# fmc-host-io-breakout.net
KiCad netlist of a schematic drawn in EAGLE
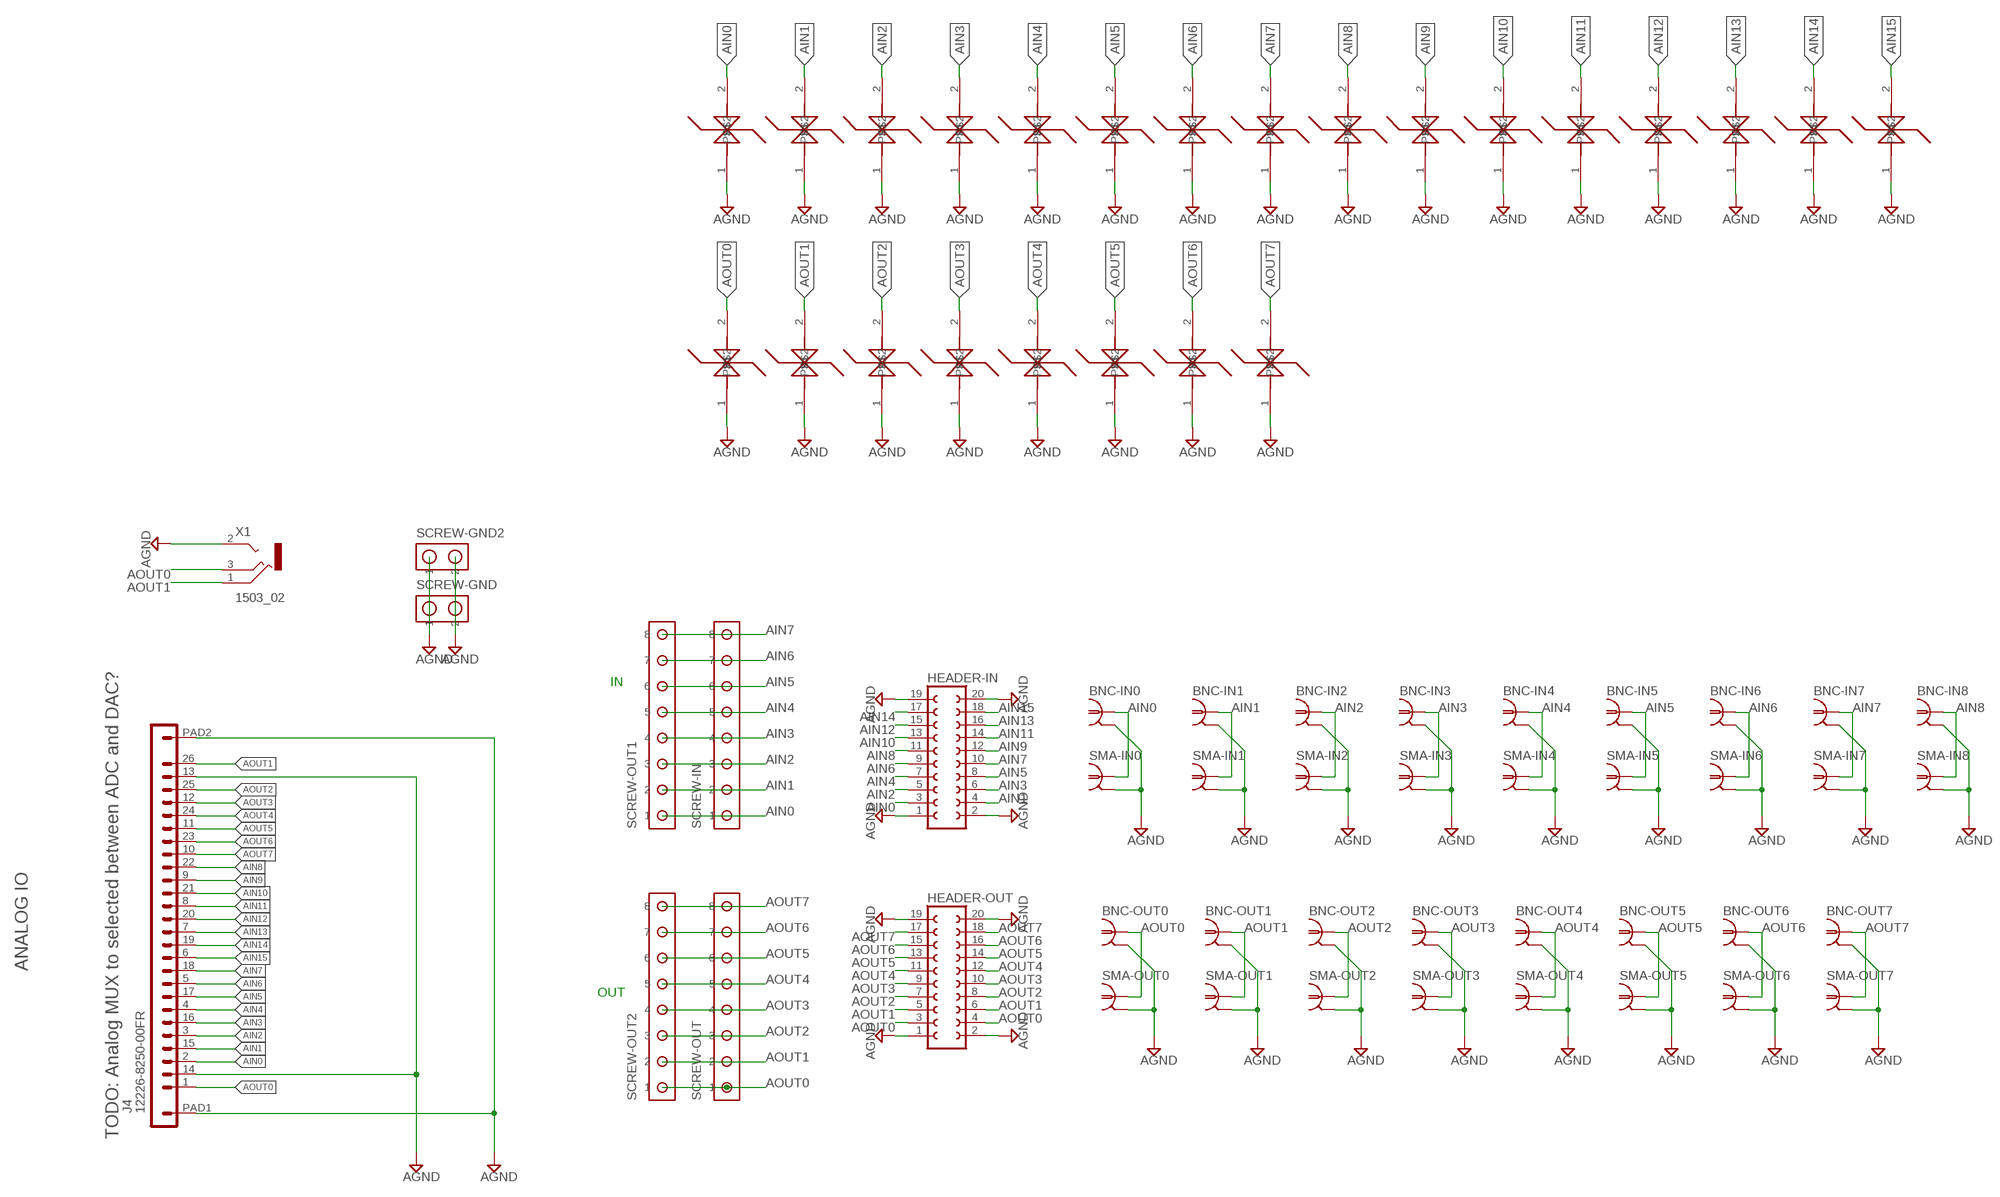
[diagram p0: schematic, sheet 1, part 1 of 2]
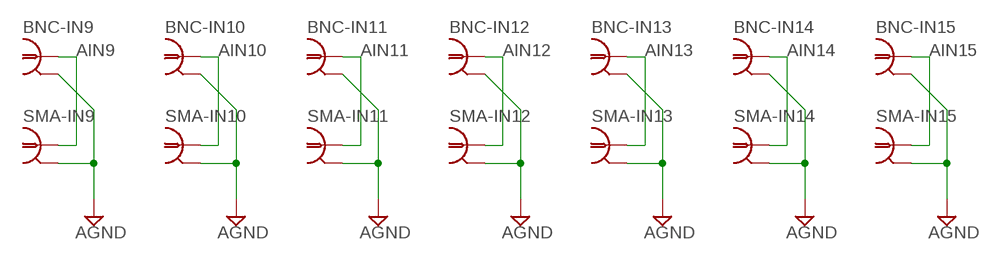
[diagram p1: schematic, sheet 1, part 2 of 2]

(export (version "E")
  (design (tool "Eeschema 10.0.6"))
  (components
    (comp (ref "BNC-IN0")
      (value "COAX_B35N61")
      (footprint "eagle-import:B35N61")
      (libsource (lib "eagle-import") (part "COAX_B35N61"))
    )
    (comp (ref "BNC-IN1")
      (value "COAX_B35N61")
      (footprint "eagle-import:B35N61")
      (libsource (lib "eagle-import") (part "COAX_B35N61"))
    )
    (comp (ref "BNC-IN2")
      (value "COAX_B35N61")
      (footprint "eagle-import:B35N61")
      (libsource (lib "eagle-import") (part "COAX_B35N61"))
    )
    (comp (ref "BNC-IN3")
      (value "COAX_B35N61")
      (footprint "eagle-import:B35N61")
      (libsource (lib "eagle-import") (part "COAX_B35N61"))
    )
    (comp (ref "BNC-IN4")
      (value "COAX_B35N61")
      (footprint "eagle-import:B35N61")
      (libsource (lib "eagle-import") (part "COAX_B35N61"))
    )
    (comp (ref "BNC-IN5")
      (value "COAX_B35N61")
      (footprint "eagle-import:B35N61")
      (libsource (lib "eagle-import") (part "COAX_B35N61"))
    )
    (comp (ref "BNC-IN6")
      (value "COAX_B35N61")
      (footprint "eagle-import:B35N61")
      (libsource (lib "eagle-import") (part "COAX_B35N61"))
    )
    (comp (ref "BNC-IN7")
      (value "COAX_B35N61")
      (footprint "eagle-import:B35N61")
      (libsource (lib "eagle-import") (part "COAX_B35N61"))
    )
    (comp (ref "BNC-IN8")
      (value "COAX_B35N61")
      (footprint "eagle-import:B35N61")
      (libsource (lib "eagle-import") (part "COAX_B35N61"))
    )
    (comp (ref "BNC-IN9")
      (value "COAX_B35N61")
      (footprint "eagle-import:B35N61")
      (libsource (lib "eagle-import") (part "COAX_B35N61"))
    )
    (comp (ref "BNC-IN10")
      (value "COAX_B35N61")
      (footprint "eagle-import:B35N61")
      (libsource (lib "eagle-import") (part "COAX_B35N61"))
    )
    (comp (ref "BNC-IN11")
      (value "COAX_B35N61")
      (footprint "eagle-import:B35N61")
      (libsource (lib "eagle-import") (part "COAX_B35N61"))
    )
    (comp (ref "BNC-IN12")
      (value "COAX_B35N61")
      (footprint "eagle-import:B35N61")
      (libsource (lib "eagle-import") (part "COAX_B35N61"))
    )
    (comp (ref "BNC-IN13")
      (value "COAX_B35N61")
      (footprint "eagle-import:B35N61")
      (libsource (lib "eagle-import") (part "COAX_B35N61"))
    )
    (comp (ref "BNC-IN14")
      (value "COAX_B35N61")
      (footprint "eagle-import:B35N61")
      (libsource (lib "eagle-import") (part "COAX_B35N61"))
    )
    (comp (ref "BNC-IN15")
      (value "COAX_B35N61")
      (footprint "eagle-import:B35N61")
      (libsource (lib "eagle-import") (part "COAX_B35N61"))
    )
    (comp (ref "BNC-OUT0")
      (value "COAX_B35N61")
      (footprint "eagle-import:B35N61")
      (libsource (lib "eagle-import") (part "COAX_B35N61"))
    )
    (comp (ref "BNC-OUT1")
      (value "COAX_B35N61")
      (footprint "eagle-import:B35N61")
      (libsource (lib "eagle-import") (part "COAX_B35N61"))
    )
    (comp (ref "BNC-OUT2")
      (value "COAX_B35N61")
      (footprint "eagle-import:B35N61")
      (libsource (lib "eagle-import") (part "COAX_B35N61"))
    )
    (comp (ref "BNC-OUT3")
      (value "COAX_B35N61")
      (footprint "eagle-import:B35N61")
      (libsource (lib "eagle-import") (part "COAX_B35N61"))
    )
    (comp (ref "BNC-OUT4")
      (value "COAX_B35N61")
      (footprint "eagle-import:B35N61")
      (libsource (lib "eagle-import") (part "COAX_B35N61"))
    )
    (comp (ref "BNC-OUT5")
      (value "COAX_B35N61")
      (footprint "eagle-import:B35N61")
      (libsource (lib "eagle-import") (part "COAX_B35N61"))
    )
    (comp (ref "BNC-OUT6")
      (value "COAX_B35N61")
      (footprint "eagle-import:B35N61")
      (libsource (lib "eagle-import") (part "COAX_B35N61"))
    )
    (comp (ref "BNC-OUT7")
      (value "COAX_B35N61")
      (footprint "eagle-import:B35N61")
      (libsource (lib "eagle-import") (part "COAX_B35N61"))
    )
    (comp (ref "HEADER-IN")
      (value "FE10-2")
      (footprint "eagle-import:FE10-2")
      (libsource (lib "eagle-import") (part "FE10-2"))
    )
    (comp (ref "HEADER-OUT")
      (value "FE10-2")
      (footprint "eagle-import:FE10-2")
      (libsource (lib "eagle-import") (part "FE10-2"))
    )
    (comp (ref "J4")
      (value "12226-8250-00FR")
      (footprint "eagle-import:12226-82X0-00XX")
      (libsource (lib "eagle-import") (part "PINHD-1X26_122"))
    )
    (comp (ref "SCREW-GND")
      (value "SCREW2")
      (footprint "eagle-import:SCREW2")
      (libsource (lib "eagle-import") (part "SCREW2"))
    )
    (comp (ref "SCREW-GND2")
      (value "SCREW2")
      (footprint "eagle-import:SCREW2")
      (libsource (lib "eagle-import") (part "SCREW2"))
    )
    (comp (ref "SCREW-IN")
      (value "SCREW8")
      (footprint "eagle-import:SCREW8")
      (libsource (lib "eagle-import") (part "SCREW8"))
    )
    (comp (ref "SCREW-OUT")
      (value "SCREW8")
      (footprint "eagle-import:SCREW8")
      (libsource (lib "eagle-import") (part "SCREW8"))
    )
    (comp (ref "SCREW-OUT1")
      (value "SCREW8")
      (footprint "eagle-import:SCREW8")
      (libsource (lib "eagle-import") (part "SCREW8"))
    )
    (comp (ref "SCREW-OUT2")
      (value "SCREW8")
      (footprint "eagle-import:SCREW8")
      (libsource (lib "eagle-import") (part "SCREW8"))
    )
    (comp (ref "SMA-IN0")
      (value "COAX_SMA-VERT")
      (footprint "eagle-import:SMA_JACK_142-0701-201")
      (libsource (lib "eagle-import") (part "COAX_SMA-VERT"))
    )
    (comp (ref "SMA-IN1")
      (value "COAX_SMA-VERT")
      (footprint "eagle-import:SMA_JACK_142-0701-201")
      (libsource (lib "eagle-import") (part "COAX_SMA-VERT"))
    )
    (comp (ref "SMA-IN2")
      (value "COAX_SMA-VERT")
      (footprint "eagle-import:SMA_JACK_142-0701-201")
      (libsource (lib "eagle-import") (part "COAX_SMA-VERT"))
    )
    (comp (ref "SMA-IN3")
      (value "COAX_SMA-VERT")
      (footprint "eagle-import:SMA_JACK_142-0701-201")
      (libsource (lib "eagle-import") (part "COAX_SMA-VERT"))
    )
    (comp (ref "SMA-IN4")
      (value "COAX_SMA-VERT")
      (footprint "eagle-import:SMA_JACK_142-0701-201")
      (libsource (lib "eagle-import") (part "COAX_SMA-VERT"))
    )
    (comp (ref "SMA-IN5")
      (value "COAX_SMA-VERT")
      (footprint "eagle-import:SMA_JACK_142-0701-201")
      (libsource (lib "eagle-import") (part "COAX_SMA-VERT"))
    )
    (comp (ref "SMA-IN6")
      (value "COAX_SMA-VERT")
      (footprint "eagle-import:SMA_JACK_142-0701-201")
      (libsource (lib "eagle-import") (part "COAX_SMA-VERT"))
    )
    (comp (ref "SMA-IN7")
      (value "COAX_SMA-VERT")
      (footprint "eagle-import:SMA_JACK_142-0701-201")
      (libsource (lib "eagle-import") (part "COAX_SMA-VERT"))
    )
    (comp (ref "SMA-IN8")
      (value "COAX_SMA-VERT")
      (footprint "eagle-import:SMA_JACK_142-0701-201")
      (libsource (lib "eagle-import") (part "COAX_SMA-VERT"))
    )
    (comp (ref "SMA-IN9")
      (value "COAX_SMA-VERT")
      (footprint "eagle-import:SMA_JACK_142-0701-201")
      (libsource (lib "eagle-import") (part "COAX_SMA-VERT"))
    )
    (comp (ref "SMA-IN10")
      (value "COAX_SMA-VERT")
      (footprint "eagle-import:SMA_JACK_142-0701-201")
      (libsource (lib "eagle-import") (part "COAX_SMA-VERT"))
    )
    (comp (ref "SMA-IN11")
      (value "COAX_SMA-VERT")
      (footprint "eagle-import:SMA_JACK_142-0701-201")
      (libsource (lib "eagle-import") (part "COAX_SMA-VERT"))
    )
    (comp (ref "SMA-IN12")
      (value "COAX_SMA-VERT")
      (footprint "eagle-import:SMA_JACK_142-0701-201")
      (libsource (lib "eagle-import") (part "COAX_SMA-VERT"))
    )
    (comp (ref "SMA-IN13")
      (value "COAX_SMA-VERT")
      (footprint "eagle-import:SMA_JACK_142-0701-201")
      (libsource (lib "eagle-import") (part "COAX_SMA-VERT"))
    )
    (comp (ref "SMA-IN14")
      (value "COAX_SMA-VERT")
      (footprint "eagle-import:SMA_JACK_142-0701-201")
      (libsource (lib "eagle-import") (part "COAX_SMA-VERT"))
    )
    (comp (ref "SMA-IN15")
      (value "COAX_SMA-VERT")
      (footprint "eagle-import:SMA_JACK_142-0701-201")
      (libsource (lib "eagle-import") (part "COAX_SMA-VERT"))
    )
    (comp (ref "SMA-OUT0")
      (value "COAX_SMA-VERT")
      (footprint "eagle-import:SMA_JACK_142-0701-201")
      (libsource (lib "eagle-import") (part "COAX_SMA-VERT"))
    )
    (comp (ref "SMA-OUT1")
      (value "COAX_SMA-VERT")
      (footprint "eagle-import:SMA_JACK_142-0701-201")
      (libsource (lib "eagle-import") (part "COAX_SMA-VERT"))
    )
    (comp (ref "SMA-OUT2")
      (value "COAX_SMA-VERT")
      (footprint "eagle-import:SMA_JACK_142-0701-201")
      (libsource (lib "eagle-import") (part "COAX_SMA-VERT"))
    )
    (comp (ref "SMA-OUT3")
      (value "COAX_SMA-VERT")
      (footprint "eagle-import:SMA_JACK_142-0701-201")
      (libsource (lib "eagle-import") (part "COAX_SMA-VERT"))
    )
    (comp (ref "SMA-OUT4")
      (value "COAX_SMA-VERT")
      (footprint "eagle-import:SMA_JACK_142-0701-201")
      (libsource (lib "eagle-import") (part "COAX_SMA-VERT"))
    )
    (comp (ref "SMA-OUT5")
      (value "COAX_SMA-VERT")
      (footprint "eagle-import:SMA_JACK_142-0701-201")
      (libsource (lib "eagle-import") (part "COAX_SMA-VERT"))
    )
    (comp (ref "SMA-OUT6")
      (value "COAX_SMA-VERT")
      (footprint "eagle-import:SMA_JACK_142-0701-201")
      (libsource (lib "eagle-import") (part "COAX_SMA-VERT"))
    )
    (comp (ref "SMA-OUT7")
      (value "COAX_SMA-VERT")
      (footprint "eagle-import:SMA_JACK_142-0701-201")
      (libsource (lib "eagle-import") (part "COAX_SMA-VERT"))
    )
    (comp (ref "U$1")
      (value "DIODE-ESD-BIDIRECTIONALDO-214AA")
      (footprint "eagle-import:DIOC7026X260")
      (libsource (lib "eagle-import") (part "DIODE-ESD-BIDIRECTIONALDO-214AA"))
    )
    (comp (ref "U$2")
      (value "DIODE-ESD-BIDIRECTIONALDO-214AA")
      (footprint "eagle-import:DIOC7026X260")
      (libsource (lib "eagle-import") (part "DIODE-ESD-BIDIRECTIONALDO-214AA"))
    )
    (comp (ref "U$3")
      (value "DIODE-ESD-BIDIRECTIONALDO-214AA")
      (footprint "eagle-import:DIOC7026X260")
      (libsource (lib "eagle-import") (part "DIODE-ESD-BIDIRECTIONALDO-214AA"))
    )
    (comp (ref "U$4")
      (value "DIODE-ESD-BIDIRECTIONALDO-214AA")
      (footprint "eagle-import:DIOC7026X260")
      (libsource (lib "eagle-import") (part "DIODE-ESD-BIDIRECTIONALDO-214AA"))
    )
    (comp (ref "U$5")
      (value "DIODE-ESD-BIDIRECTIONALDO-214AA")
      (footprint "eagle-import:DIOC7026X260")
      (libsource (lib "eagle-import") (part "DIODE-ESD-BIDIRECTIONALDO-214AA"))
    )
    (comp (ref "U$6")
      (value "DIODE-ESD-BIDIRECTIONALDO-214AA")
      (footprint "eagle-import:DIOC7026X260")
      (libsource (lib "eagle-import") (part "DIODE-ESD-BIDIRECTIONALDO-214AA"))
    )
    (comp (ref "U$7")
      (value "DIODE-ESD-BIDIRECTIONALDO-214AA")
      (footprint "eagle-import:DIOC7026X260")
      (libsource (lib "eagle-import") (part "DIODE-ESD-BIDIRECTIONALDO-214AA"))
    )
    (comp (ref "U$8")
      (value "DIODE-ESD-BIDIRECTIONALDO-214AA")
      (footprint "eagle-import:DIOC7026X260")
      (libsource (lib "eagle-import") (part "DIODE-ESD-BIDIRECTIONALDO-214AA"))
    )
    (comp (ref "U$9")
      (value "DIODE-ESD-BIDIRECTIONALDO-214AA")
      (footprint "eagle-import:DIOC7026X260")
      (libsource (lib "eagle-import") (part "DIODE-ESD-BIDIRECTIONALDO-214AA"))
    )
    (comp (ref "U$10")
      (value "DIODE-ESD-BIDIRECTIONALDO-214AA")
      (footprint "eagle-import:DIOC7026X260")
      (libsource (lib "eagle-import") (part "DIODE-ESD-BIDIRECTIONALDO-214AA"))
    )
    (comp (ref "U$11")
      (value "DIODE-ESD-BIDIRECTIONALDO-214AA")
      (footprint "eagle-import:DIOC7026X260")
      (libsource (lib "eagle-import") (part "DIODE-ESD-BIDIRECTIONALDO-214AA"))
    )
    (comp (ref "U$12")
      (value "DIODE-ESD-BIDIRECTIONALDO-214AA")
      (footprint "eagle-import:DIOC7026X260")
      (libsource (lib "eagle-import") (part "DIODE-ESD-BIDIRECTIONALDO-214AA"))
    )
    (comp (ref "U$13")
      (value "DIODE-ESD-BIDIRECTIONALDO-214AA")
      (footprint "eagle-import:DIOC7026X260")
      (libsource (lib "eagle-import") (part "DIODE-ESD-BIDIRECTIONALDO-214AA"))
    )
    (comp (ref "U$14")
      (value "DIODE-ESD-BIDIRECTIONALDO-214AA")
      (footprint "eagle-import:DIOC7026X260")
      (libsource (lib "eagle-import") (part "DIODE-ESD-BIDIRECTIONALDO-214AA"))
    )
    (comp (ref "U$15")
      (value "DIODE-ESD-BIDIRECTIONALDO-214AA")
      (footprint "eagle-import:DIOC7026X260")
      (libsource (lib "eagle-import") (part "DIODE-ESD-BIDIRECTIONALDO-214AA"))
    )
    (comp (ref "U$16")
      (value "DIODE-ESD-BIDIRECTIONALDO-214AA")
      (footprint "eagle-import:DIOC7026X260")
      (libsource (lib "eagle-import") (part "DIODE-ESD-BIDIRECTIONALDO-214AA"))
    )
    (comp (ref "U$17")
      (value "DIODE-ESD-BIDIRECTIONALDO-214AA")
      (footprint "eagle-import:DIOC7026X260")
      (libsource (lib "eagle-import") (part "DIODE-ESD-BIDIRECTIONALDO-214AA"))
    )
    (comp (ref "U$18")
      (value "DIODE-ESD-BIDIRECTIONALDO-214AA")
      (footprint "eagle-import:DIOC7026X260")
      (libsource (lib "eagle-import") (part "DIODE-ESD-BIDIRECTIONALDO-214AA"))
    )
    (comp (ref "U$19")
      (value "DIODE-ESD-BIDIRECTIONALDO-214AA")
      (footprint "eagle-import:DIOC7026X260")
      (libsource (lib "eagle-import") (part "DIODE-ESD-BIDIRECTIONALDO-214AA"))
    )
    (comp (ref "U$20")
      (value "DIODE-ESD-BIDIRECTIONALDO-214AA")
      (footprint "eagle-import:DIOC7026X260")
      (libsource (lib "eagle-import") (part "DIODE-ESD-BIDIRECTIONALDO-214AA"))
    )
    (comp (ref "U$21")
      (value "DIODE-ESD-BIDIRECTIONALDO-214AA")
      (footprint "eagle-import:DIOC7026X260")
      (libsource (lib "eagle-import") (part "DIODE-ESD-BIDIRECTIONALDO-214AA"))
    )
    (comp (ref "U$22")
      (value "DIODE-ESD-BIDIRECTIONALDO-214AA")
      (footprint "eagle-import:DIOC7026X260")
      (libsource (lib "eagle-import") (part "DIODE-ESD-BIDIRECTIONALDO-214AA"))
    )
    (comp (ref "U$23")
      (value "DIODE-ESD-BIDIRECTIONALDO-214AA")
      (footprint "eagle-import:DIOC7026X260")
      (libsource (lib "eagle-import") (part "DIODE-ESD-BIDIRECTIONALDO-214AA"))
    )
    (comp (ref "U$24")
      (value "DIODE-ESD-BIDIRECTIONALDO-214AA")
      (footprint "eagle-import:DIOC7026X260")
      (libsource (lib "eagle-import") (part "DIODE-ESD-BIDIRECTIONALDO-214AA"))
    )
    (comp (ref "X1")
      (value "1503_02")
      (footprint "eagle-import:1503_02")
      (libsource (lib "eagle-import") (part "1503_02"))
    )
  )
  (nets
    (net (code "1") (name "AGND") (class "Default")
      (node (ref "BNC-IN0") (pin "2") (pinfunction "2_2") (pintype "passive"))
      (node (ref "BNC-IN0") (pin "3") (pinfunction "2_3") (pintype "passive"))
      (node (ref "BNC-IN0") (pin "4") (pinfunction "2_4") (pintype "passive"))
      (node (ref "BNC-IN0") (pin "5") (pinfunction "2_5") (pintype "passive"))
      (node (ref "BNC-IN1") (pin "2") (pinfunction "2_2") (pintype "passive"))
      (node (ref "BNC-IN1") (pin "3") (pinfunction "2_3") (pintype "passive"))
      (node (ref "BNC-IN1") (pin "4") (pinfunction "2_4") (pintype "passive"))
      (node (ref "BNC-IN1") (pin "5") (pinfunction "2_5") (pintype "passive"))
      (node (ref "BNC-IN10") (pin "2") (pinfunction "2_2") (pintype "passive"))
      (node (ref "BNC-IN10") (pin "3") (pinfunction "2_3") (pintype "passive"))
      (node (ref "BNC-IN10") (pin "4") (pinfunction "2_4") (pintype "passive"))
      (node (ref "BNC-IN10") (pin "5") (pinfunction "2_5") (pintype "passive"))
      (node (ref "BNC-IN11") (pin "2") (pinfunction "2_2") (pintype "passive"))
      (node (ref "BNC-IN11") (pin "3") (pinfunction "2_3") (pintype "passive"))
      (node (ref "BNC-IN11") (pin "4") (pinfunction "2_4") (pintype "passive"))
      (node (ref "BNC-IN11") (pin "5") (pinfunction "2_5") (pintype "passive"))
      (node (ref "BNC-IN12") (pin "2") (pinfunction "2_2") (pintype "passive"))
      (node (ref "BNC-IN12") (pin "3") (pinfunction "2_3") (pintype "passive"))
      (node (ref "BNC-IN12") (pin "4") (pinfunction "2_4") (pintype "passive"))
      (node (ref "BNC-IN12") (pin "5") (pinfunction "2_5") (pintype "passive"))
      (node (ref "BNC-IN13") (pin "2") (pinfunction "2_2") (pintype "passive"))
      (node (ref "BNC-IN13") (pin "3") (pinfunction "2_3") (pintype "passive"))
      (node (ref "BNC-IN13") (pin "4") (pinfunction "2_4") (pintype "passive"))
      (node (ref "BNC-IN13") (pin "5") (pinfunction "2_5") (pintype "passive"))
      (node (ref "BNC-IN14") (pin "2") (pinfunction "2_2") (pintype "passive"))
      (node (ref "BNC-IN14") (pin "3") (pinfunction "2_3") (pintype "passive"))
      (node (ref "BNC-IN14") (pin "4") (pinfunction "2_4") (pintype "passive"))
      (node (ref "BNC-IN14") (pin "5") (pinfunction "2_5") (pintype "passive"))
      (node (ref "BNC-IN15") (pin "2") (pinfunction "2_2") (pintype "passive"))
      (node (ref "BNC-IN15") (pin "3") (pinfunction "2_3") (pintype "passive"))
      (node (ref "BNC-IN15") (pin "4") (pinfunction "2_4") (pintype "passive"))
      (node (ref "BNC-IN15") (pin "5") (pinfunction "2_5") (pintype "passive"))
      (node (ref "BNC-IN2") (pin "2") (pinfunction "2_2") (pintype "passive"))
      (node (ref "BNC-IN2") (pin "3") (pinfunction "2_3") (pintype "passive"))
      (node (ref "BNC-IN2") (pin "4") (pinfunction "2_4") (pintype "passive"))
      (node (ref "BNC-IN2") (pin "5") (pinfunction "2_5") (pintype "passive"))
      (node (ref "BNC-IN3") (pin "2") (pinfunction "2_2") (pintype "passive"))
      (node (ref "BNC-IN3") (pin "3") (pinfunction "2_3") (pintype "passive"))
      (node (ref "BNC-IN3") (pin "4") (pinfunction "2_4") (pintype "passive"))
      (node (ref "BNC-IN3") (pin "5") (pinfunction "2_5") (pintype "passive"))
      (node (ref "BNC-IN4") (pin "2") (pinfunction "2_2") (pintype "passive"))
      (node (ref "BNC-IN4") (pin "3") (pinfunction "2_3") (pintype "passive"))
      (node (ref "BNC-IN4") (pin "4") (pinfunction "2_4") (pintype "passive"))
      (node (ref "BNC-IN4") (pin "5") (pinfunction "2_5") (pintype "passive"))
      (node (ref "BNC-IN5") (pin "2") (pinfunction "2_2") (pintype "passive"))
      (node (ref "BNC-IN5") (pin "3") (pinfunction "2_3") (pintype "passive"))
      (node (ref "BNC-IN5") (pin "4") (pinfunction "2_4") (pintype "passive"))
      (node (ref "BNC-IN5") (pin "5") (pinfunction "2_5") (pintype "passive"))
      (node (ref "BNC-IN6") (pin "2") (pinfunction "2_2") (pintype "passive"))
      (node (ref "BNC-IN6") (pin "3") (pinfunction "2_3") (pintype "passive"))
      (node (ref "BNC-IN6") (pin "4") (pinfunction "2_4") (pintype "passive"))
      (node (ref "BNC-IN6") (pin "5") (pinfunction "2_5") (pintype "passive"))
      (node (ref "BNC-IN7") (pin "2") (pinfunction "2_2") (pintype "passive"))
      (node (ref "BNC-IN7") (pin "3") (pinfunction "2_3") (pintype "passive"))
      (node (ref "BNC-IN7") (pin "4") (pinfunction "2_4") (pintype "passive"))
      (node (ref "BNC-IN7") (pin "5") (pinfunction "2_5") (pintype "passive"))
      (node (ref "BNC-IN8") (pin "2") (pinfunction "2_2") (pintype "passive"))
      (node (ref "BNC-IN8") (pin "3") (pinfunction "2_3") (pintype "passive"))
      (node (ref "BNC-IN8") (pin "4") (pinfunction "2_4") (pintype "passive"))
      (node (ref "BNC-IN8") (pin "5") (pinfunction "2_5") (pintype "passive"))
      (node (ref "BNC-IN9") (pin "2") (pinfunction "2_2") (pintype "passive"))
      (node (ref "BNC-IN9") (pin "3") (pinfunction "2_3") (pintype "passive"))
      (node (ref "BNC-IN9") (pin "4") (pinfunction "2_4") (pintype "passive"))
      (node (ref "BNC-IN9") (pin "5") (pinfunction "2_5") (pintype "passive"))
      (node (ref "BNC-OUT0") (pin "2") (pinfunction "2_2") (pintype "passive"))
      (node (ref "BNC-OUT0") (pin "3") (pinfunction "2_3") (pintype "passive"))
      (node (ref "BNC-OUT0") (pin "4") (pinfunction "2_4") (pintype "passive"))
      (node (ref "BNC-OUT0") (pin "5") (pinfunction "2_5") (pintype "passive"))
      (node (ref "BNC-OUT1") (pin "2") (pinfunction "2_2") (pintype "passive"))
      (node (ref "BNC-OUT1") (pin "3") (pinfunction "2_3") (pintype "passive"))
      (node (ref "BNC-OUT1") (pin "4") (pinfunction "2_4") (pintype "passive"))
      (node (ref "BNC-OUT1") (pin "5") (pinfunction "2_5") (pintype "passive"))
      (node (ref "BNC-OUT2") (pin "2") (pinfunction "2_2") (pintype "passive"))
      (node (ref "BNC-OUT2") (pin "3") (pinfunction "2_3") (pintype "passive"))
      (node (ref "BNC-OUT2") (pin "4") (pinfunction "2_4") (pintype "passive"))
      (node (ref "BNC-OUT2") (pin "5") (pinfunction "2_5") (pintype "passive"))
      (node (ref "BNC-OUT3") (pin "2") (pinfunction "2_2") (pintype "passive"))
      (node (ref "BNC-OUT3") (pin "3") (pinfunction "2_3") (pintype "passive"))
      (node (ref "BNC-OUT3") (pin "4") (pinfunction "2_4") (pintype "passive"))
      (node (ref "BNC-OUT3") (pin "5") (pinfunction "2_5") (pintype "passive"))
      (node (ref "BNC-OUT4") (pin "2") (pinfunction "2_2") (pintype "passive"))
      (node (ref "BNC-OUT4") (pin "3") (pinfunction "2_3") (pintype "passive"))
      (node (ref "BNC-OUT4") (pin "4") (pinfunction "2_4") (pintype "passive"))
      (node (ref "BNC-OUT4") (pin "5") (pinfunction "2_5") (pintype "passive"))
      (node (ref "BNC-OUT5") (pin "2") (pinfunction "2_2") (pintype "passive"))
      (node (ref "BNC-OUT5") (pin "3") (pinfunction "2_3") (pintype "passive"))
      (node (ref "BNC-OUT5") (pin "4") (pinfunction "2_4") (pintype "passive"))
      (node (ref "BNC-OUT5") (pin "5") (pinfunction "2_5") (pintype "passive"))
      (node (ref "BNC-OUT6") (pin "2") (pinfunction "2_2") (pintype "passive"))
      (node (ref "BNC-OUT6") (pin "3") (pinfunction "2_3") (pintype "passive"))
      (node (ref "BNC-OUT6") (pin "4") (pinfunction "2_4") (pintype "passive"))
      (node (ref "BNC-OUT6") (pin "5") (pinfunction "2_5") (pintype "passive"))
      (node (ref "BNC-OUT7") (pin "2") (pinfunction "2_2") (pintype "passive"))
      (node (ref "BNC-OUT7") (pin "3") (pinfunction "2_3") (pintype "passive"))
      (node (ref "BNC-OUT7") (pin "4") (pinfunction "2_4") (pintype "passive"))
      (node (ref "BNC-OUT7") (pin "5") (pinfunction "2_5") (pintype "passive"))
      (node (ref "HEADER-IN") (pin "1") (pinfunction "1_1") (pintype "passive"))
      (node (ref "HEADER-IN") (pin "19") (pinfunction "19_19") (pintype "passive"))
      (node (ref "HEADER-IN") (pin "2") (pinfunction "2_2") (pintype "passive"))
      (node (ref "HEADER-IN") (pin "20") (pinfunction "20_20") (pintype "passive"))
      (node (ref "HEADER-OUT") (pin "1") (pinfunction "1_1") (pintype "passive"))
      (node (ref "HEADER-OUT") (pin "19") (pinfunction "19_19") (pintype "passive"))
      (node (ref "HEADER-OUT") (pin "2") (pinfunction "2_2") (pintype "passive"))
      (node (ref "HEADER-OUT") (pin "20") (pinfunction "20_20") (pintype "passive"))
      (node (ref "J4") (pin "13") (pinfunction "13_13") (pintype "bidirectional"))
      (node (ref "J4") (pin "14") (pinfunction "14_14") (pintype "bidirectional"))
      (node (ref "J4") (pin "PAD1") (pinfunction "PAD1_PAD1") (pintype "bidirectional"))
      (node (ref "J4") (pin "PAD2") (pinfunction "PAD2_PAD2") (pintype "bidirectional"))
      (node (ref "SCREW-GND") (pin "P$1") (pinfunction "1_P$1") (pintype "passive"))
      (node (ref "SCREW-GND") (pin "P$2") (pinfunction "2_P$2") (pintype "passive"))
      (node (ref "SCREW-GND2") (pin "P$1") (pinfunction "1_P$1") (pintype "passive"))
      (node (ref "SCREW-GND2") (pin "P$2") (pinfunction "2_P$2") (pintype "passive"))
      (node (ref "SMA-IN0") (pin "GND$1") (pinfunction "2_GND$1") (pintype "passive"))
      (node (ref "SMA-IN0") (pin "GND$2") (pinfunction "2_GND$2") (pintype "passive"))
      (node (ref "SMA-IN0") (pin "GND$3") (pinfunction "2_GND$3") (pintype "passive"))
      (node (ref "SMA-IN0") (pin "GND$4") (pinfunction "2_GND$4") (pintype "passive"))
      (node (ref "SMA-IN1") (pin "GND$1") (pinfunction "2_GND$1") (pintype "passive"))
      (node (ref "SMA-IN1") (pin "GND$2") (pinfunction "2_GND$2") (pintype "passive"))
      (node (ref "SMA-IN1") (pin "GND$3") (pinfunction "2_GND$3") (pintype "passive"))
      (node (ref "SMA-IN1") (pin "GND$4") (pinfunction "2_GND$4") (pintype "passive"))
      (node (ref "SMA-IN10") (pin "GND$1") (pinfunction "2_GND$1") (pintype "passive"))
      (node (ref "SMA-IN10") (pin "GND$2") (pinfunction "2_GND$2") (pintype "passive"))
      (node (ref "SMA-IN10") (pin "GND$3") (pinfunction "2_GND$3") (pintype "passive"))
      (node (ref "SMA-IN10") (pin "GND$4") (pinfunction "2_GND$4") (pintype "passive"))
      (node (ref "SMA-IN11") (pin "GND$1") (pinfunction "2_GND$1") (pintype "passive"))
      (node (ref "SMA-IN11") (pin "GND$2") (pinfunction "2_GND$2") (pintype "passive"))
      (node (ref "SMA-IN11") (pin "GND$3") (pinfunction "2_GND$3") (pintype "passive"))
      (node (ref "SMA-IN11") (pin "GND$4") (pinfunction "2_GND$4") (pintype "passive"))
      (node (ref "SMA-IN12") (pin "GND$1") (pinfunction "2_GND$1") (pintype "passive"))
      (node (ref "SMA-IN12") (pin "GND$2") (pinfunction "2_GND$2") (pintype "passive"))
      (node (ref "SMA-IN12") (pin "GND$3") (pinfunction "2_GND$3") (pintype "passive"))
      (node (ref "SMA-IN12") (pin "GND$4") (pinfunction "2_GND$4") (pintype "passive"))
      (node (ref "SMA-IN13") (pin "GND$1") (pinfunction "2_GND$1") (pintype "passive"))
      (node (ref "SMA-IN13") (pin "GND$2") (pinfunction "2_GND$2") (pintype "passive"))
      (node (ref "SMA-IN13") (pin "GND$3") (pinfunction "2_GND$3") (pintype "passive"))
      (node (ref "SMA-IN13") (pin "GND$4") (pinfunction "2_GND$4") (pintype "passive"))
      (node (ref "SMA-IN14") (pin "GND$1") (pinfunction "2_GND$1") (pintype "passive"))
      (node (ref "SMA-IN14") (pin "GND$2") (pinfunction "2_GND$2") (pintype "passive"))
      (node (ref "SMA-IN14") (pin "GND$3") (pinfunction "2_GND$3") (pintype "passive"))
      (node (ref "SMA-IN14") (pin "GND$4") (pinfunction "2_GND$4") (pintype "passive"))
      (node (ref "SMA-IN15") (pin "GND$1") (pinfunction "2_GND$1") (pintype "passive"))
      (node (ref "SMA-IN15") (pin "GND$2") (pinfunction "2_GND$2") (pintype "passive"))
      (node (ref "SMA-IN15") (pin "GND$3") (pinfunction "2_GND$3") (pintype "passive"))
      (node (ref "SMA-IN15") (pin "GND$4") (pinfunction "2_GND$4") (pintype "passive"))
      (node (ref "SMA-IN2") (pin "GND$1") (pinfunction "2_GND$1") (pintype "passive"))
      (node (ref "SMA-IN2") (pin "GND$2") (pinfunction "2_GND$2") (pintype "passive"))
      (node (ref "SMA-IN2") (pin "GND$3") (pinfunction "2_GND$3") (pintype "passive"))
      (node (ref "SMA-IN2") (pin "GND$4") (pinfunction "2_GND$4") (pintype "passive"))
      (node (ref "SMA-IN3") (pin "GND$1") (pinfunction "2_GND$1") (pintype "passive"))
      (node (ref "SMA-IN3") (pin "GND$2") (pinfunction "2_GND$2") (pintype "passive"))
      (node (ref "SMA-IN3") (pin "GND$3") (pinfunction "2_GND$3") (pintype "passive"))
      (node (ref "SMA-IN3") (pin "GND$4") (pinfunction "2_GND$4") (pintype "passive"))
      (node (ref "SMA-IN4") (pin "GND$1") (pinfunction "2_GND$1") (pintype "passive"))
      (node (ref "SMA-IN4") (pin "GND$2") (pinfunction "2_GND$2") (pintype "passive"))
      (node (ref "SMA-IN4") (pin "GND$3") (pinfunction "2_GND$3") (pintype "passive"))
      (node (ref "SMA-IN4") (pin "GND$4") (pinfunction "2_GND$4") (pintype "passive"))
      (node (ref "SMA-IN5") (pin "GND$1") (pinfunction "2_GND$1") (pintype "passive"))
      (node (ref "SMA-IN5") (pin "GND$2") (pinfunction "2_GND$2") (pintype "passive"))
      (node (ref "SMA-IN5") (pin "GND$3") (pinfunction "2_GND$3") (pintype "passive"))
      (node (ref "SMA-IN5") (pin "GND$4") (pinfunction "2_GND$4") (pintype "passive"))
      (node (ref "SMA-IN6") (pin "GND$1") (pinfunction "2_GND$1") (pintype "passive"))
      (node (ref "SMA-IN6") (pin "GND$2") (pinfunction "2_GND$2") (pintype "passive"))
      (node (ref "SMA-IN6") (pin "GND$3") (pinfunction "2_GND$3") (pintype "passive"))
      (node (ref "SMA-IN6") (pin "GND$4") (pinfunction "2_GND$4") (pintype "passive"))
      (node (ref "SMA-IN7") (pin "GND$1") (pinfunction "2_GND$1") (pintype "passive"))
      (node (ref "SMA-IN7") (pin "GND$2") (pinfunction "2_GND$2") (pintype "passive"))
      (node (ref "SMA-IN7") (pin "GND$3") (pinfunction "2_GND$3") (pintype "passive"))
      (node (ref "SMA-IN7") (pin "GND$4") (pinfunction "2_GND$4") (pintype "passive"))
      (node (ref "SMA-IN8") (pin "GND$1") (pinfunction "2_GND$1") (pintype "passive"))
      (node (ref "SMA-IN8") (pin "GND$2") (pinfunction "2_GND$2") (pintype "passive"))
      (node (ref "SMA-IN8") (pin "GND$3") (pinfunction "2_GND$3") (pintype "passive"))
      (node (ref "SMA-IN8") (pin "GND$4") (pinfunction "2_GND$4") (pintype "passive"))
      (node (ref "SMA-IN9") (pin "GND$1") (pinfunction "2_GND$1") (pintype "passive"))
      (node (ref "SMA-IN9") (pin "GND$2") (pinfunction "2_GND$2") (pintype "passive"))
      (node (ref "SMA-IN9") (pin "GND$3") (pinfunction "2_GND$3") (pintype "passive"))
      (node (ref "SMA-IN9") (pin "GND$4") (pinfunction "2_GND$4") (pintype "passive"))
      (node (ref "SMA-OUT0") (pin "GND$1") (pinfunction "2_GND$1") (pintype "passive"))
      (node (ref "SMA-OUT0") (pin "GND$2") (pinfunction "2_GND$2") (pintype "passive"))
      (node (ref "SMA-OUT0") (pin "GND$3") (pinfunction "2_GND$3") (pintype "passive"))
      (node (ref "SMA-OUT0") (pin "GND$4") (pinfunction "2_GND$4") (pintype "passive"))
      (node (ref "SMA-OUT1") (pin "GND$1") (pinfunction "2_GND$1") (pintype "passive"))
      (node (ref "SMA-OUT1") (pin "GND$2") (pinfunction "2_GND$2") (pintype "passive"))
      (node (ref "SMA-OUT1") (pin "GND$3") (pinfunction "2_GND$3") (pintype "passive"))
      (node (ref "SMA-OUT1") (pin "GND$4") (pinfunction "2_GND$4") (pintype "passive"))
      (node (ref "SMA-OUT2") (pin "GND$1") (pinfunction "2_GND$1") (pintype "passive"))
      (node (ref "SMA-OUT2") (pin "GND$2") (pinfunction "2_GND$2") (pintype "passive"))
      (node (ref "SMA-OUT2") (pin "GND$3") (pinfunction "2_GND$3") (pintype "passive"))
      (node (ref "SMA-OUT2") (pin "GND$4") (pinfunction "2_GND$4") (pintype "passive"))
      (node (ref "SMA-OUT3") (pin "GND$1") (pinfunction "2_GND$1") (pintype "passive"))
      (node (ref "SMA-OUT3") (pin "GND$2") (pinfunction "2_GND$2") (pintype "passive"))
      (node (ref "SMA-OUT3") (pin "GND$3") (pinfunction "2_GND$3") (pintype "passive"))
      (node (ref "SMA-OUT3") (pin "GND$4") (pinfunction "2_GND$4") (pintype "passive"))
      (node (ref "SMA-OUT4") (pin "GND$1") (pinfunction "2_GND$1") (pintype "passive"))
      (node (ref "SMA-OUT4") (pin "GND$2") (pinfunction "2_GND$2") (pintype "passive"))
      (node (ref "SMA-OUT4") (pin "GND$3") (pinfunction "2_GND$3") (pintype "passive"))
      (node (ref "SMA-OUT4") (pin "GND$4") (pinfunction "2_GND$4") (pintype "passive"))
      (node (ref "SMA-OUT5") (pin "GND$1") (pinfunction "2_GND$1") (pintype "passive"))
      (node (ref "SMA-OUT5") (pin "GND$2") (pinfunction "2_GND$2") (pintype "passive"))
      (node (ref "SMA-OUT5") (pin "GND$3") (pinfunction "2_GND$3") (pintype "passive"))
      (node (ref "SMA-OUT5") (pin "GND$4") (pinfunction "2_GND$4") (pintype "passive"))
      (node (ref "SMA-OUT6") (pin "GND$1") (pinfunction "2_GND$1") (pintype "passive"))
      (node (ref "SMA-OUT6") (pin "GND$2") (pinfunction "2_GND$2") (pintype "passive"))
      (node (ref "SMA-OUT6") (pin "GND$3") (pinfunction "2_GND$3") (pintype "passive"))
      (node (ref "SMA-OUT6") (pin "GND$4") (pinfunction "2_GND$4") (pintype "passive"))
      (node (ref "SMA-OUT7") (pin "GND$1") (pinfunction "2_GND$1") (pintype "passive"))
      (node (ref "SMA-OUT7") (pin "GND$2") (pinfunction "2_GND$2") (pintype "passive"))
      (node (ref "SMA-OUT7") (pin "GND$3") (pinfunction "2_GND$3") (pintype "passive"))
      (node (ref "SMA-OUT7") (pin "GND$4") (pinfunction "2_GND$4") (pintype "passive"))
      (node (ref "U$1") (pin "1") (pinfunction "P$1_1") (pintype "bidirectional"))
      (node (ref "U$10") (pin "1") (pinfunction "P$1_1") (pintype "bidirectional"))
      (node (ref "U$11") (pin "1") (pinfunction "P$1_1") (pintype "bidirectional"))
      (node (ref "U$12") (pin "1") (pinfunction "P$1_1") (pintype "bidirectional"))
      (node (ref "U$13") (pin "1") (pinfunction "P$1_1") (pintype "bidirectional"))
      (node (ref "U$14") (pin "1") (pinfunction "P$1_1") (pintype "bidirectional"))
      (node (ref "U$15") (pin "1") (pinfunction "P$1_1") (pintype "bidirectional"))
      (node (ref "U$16") (pin "1") (pinfunction "P$1_1") (pintype "bidirectional"))
      (node (ref "U$17") (pin "1") (pinfunction "P$1_1") (pintype "bidirectional"))
      (node (ref "U$18") (pin "1") (pinfunction "P$1_1") (pintype "bidirectional"))
      (node (ref "U$19") (pin "1") (pinfunction "P$1_1") (pintype "bidirectional"))
      (node (ref "U$2") (pin "1") (pinfunction "P$1_1") (pintype "bidirectional"))
      (node (ref "U$20") (pin "1") (pinfunction "P$1_1") (pintype "bidirectional"))
      (node (ref "U$21") (pin "1") (pinfunction "P$1_1") (pintype "bidirectional"))
      (node (ref "U$22") (pin "1") (pinfunction "P$1_1") (pintype "bidirectional"))
      (node (ref "U$23") (pin "1") (pinfunction "P$1_1") (pintype "bidirectional"))
      (node (ref "U$24") (pin "1") (pinfunction "P$1_1") (pintype "bidirectional"))
      (node (ref "U$3") (pin "1") (pinfunction "P$1_1") (pintype "bidirectional"))
      (node (ref "U$4") (pin "1") (pinfunction "P$1_1") (pintype "bidirectional"))
      (node (ref "U$5") (pin "1") (pinfunction "P$1_1") (pintype "bidirectional"))
      (node (ref "U$6") (pin "1") (pinfunction "P$1_1") (pintype "bidirectional"))
      (node (ref "U$7") (pin "1") (pinfunction "P$1_1") (pintype "bidirectional"))
      (node (ref "U$8") (pin "1") (pinfunction "P$1_1") (pintype "bidirectional"))
      (node (ref "U$9") (pin "1") (pinfunction "P$1_1") (pintype "bidirectional"))
      (node (ref "X1") (pin "2") (pinfunction "2_2") (pintype "passive"))
    )
    (net (code "2") (name "AIN0") (class "Default")
      (node (ref "BNC-IN0") (pin "1") (pinfunction "1_1") (pintype "passive"))
      (node (ref "HEADER-IN") (pin "3") (pinfunction "3_3") (pintype "passive"))
      (node (ref "J4") (pin "2") (pinfunction "2_2") (pintype "bidirectional"))
      (node (ref "SCREW-IN") (pin "1") (pinfunction "1_1") (pintype "bidirectional"))
      (node (ref "SCREW-OUT1") (pin "1") (pinfunction "1_1") (pintype "bidirectional"))
      (node (ref "SMA-IN0") (pin "CLK") (pinfunction "1_CLK") (pintype "passive"))
      (node (ref "U$1") (pin "2") (pinfunction "P$2_2") (pintype "bidirectional"))
    )
    (net (code "3") (name "AIN1") (class "Default")
      (node (ref "BNC-IN1") (pin "1") (pinfunction "1_1") (pintype "passive"))
      (node (ref "HEADER-IN") (pin "4") (pinfunction "4_4") (pintype "passive"))
      (node (ref "J4") (pin "15") (pinfunction "15_15") (pintype "bidirectional"))
      (node (ref "SCREW-IN") (pin "2") (pinfunction "2_2") (pintype "bidirectional"))
      (node (ref "SCREW-OUT1") (pin "2") (pinfunction "2_2") (pintype "bidirectional"))
      (node (ref "SMA-IN1") (pin "CLK") (pinfunction "1_CLK") (pintype "passive"))
      (node (ref "U$2") (pin "2") (pinfunction "P$2_2") (pintype "bidirectional"))
    )
    (net (code "4") (name "AIN2") (class "Default")
      (node (ref "BNC-IN2") (pin "1") (pinfunction "1_1") (pintype "passive"))
      (node (ref "HEADER-IN") (pin "5") (pinfunction "5_5") (pintype "passive"))
      (node (ref "J4") (pin "3") (pinfunction "3_3") (pintype "bidirectional"))
      (node (ref "SCREW-IN") (pin "3") (pinfunction "3_3") (pintype "bidirectional"))
      (node (ref "SCREW-OUT1") (pin "3") (pinfunction "3_3") (pintype "bidirectional"))
      (node (ref "SMA-IN2") (pin "CLK") (pinfunction "1_CLK") (pintype "passive"))
      (node (ref "U$3") (pin "2") (pinfunction "P$2_2") (pintype "bidirectional"))
    )
    (net (code "5") (name "AIN3") (class "Default")
      (node (ref "BNC-IN3") (pin "1") (pinfunction "1_1") (pintype "passive"))
      (node (ref "HEADER-IN") (pin "6") (pinfunction "6_6") (pintype "passive"))
      (node (ref "J4") (pin "16") (pinfunction "16_16") (pintype "bidirectional"))
      (node (ref "SCREW-IN") (pin "4") (pinfunction "4_4") (pintype "bidirectional"))
      (node (ref "SCREW-OUT1") (pin "4") (pinfunction "4_4") (pintype "bidirectional"))
      (node (ref "SMA-IN3") (pin "CLK") (pinfunction "1_CLK") (pintype "passive"))
      (node (ref "U$4") (pin "2") (pinfunction "P$2_2") (pintype "bidirectional"))
    )
    (net (code "6") (name "AIN4") (class "Default")
      (node (ref "BNC-IN4") (pin "1") (pinfunction "1_1") (pintype "passive"))
      (node (ref "HEADER-IN") (pin "7") (pinfunction "7_7") (pintype "passive"))
      (node (ref "J4") (pin "4") (pinfunction "4_4") (pintype "bidirectional"))
      (node (ref "SCREW-IN") (pin "5") (pinfunction "5_5") (pintype "bidirectional"))
      (node (ref "SCREW-OUT1") (pin "5") (pinfunction "5_5") (pintype "bidirectional"))
      (node (ref "SMA-IN4") (pin "CLK") (pinfunction "1_CLK") (pintype "passive"))
      (node (ref "U$5") (pin "2") (pinfunction "P$2_2") (pintype "bidirectional"))
    )
    (net (code "7") (name "AIN5") (class "Default")
      (node (ref "BNC-IN5") (pin "1") (pinfunction "1_1") (pintype "passive"))
      (node (ref "HEADER-IN") (pin "8") (pinfunction "8_8") (pintype "passive"))
      (node (ref "J4") (pin "17") (pinfunction "17_17") (pintype "bidirectional"))
      (node (ref "SCREW-IN") (pin "6") (pinfunction "6_6") (pintype "bidirectional"))
      (node (ref "SCREW-OUT1") (pin "6") (pinfunction "6_6") (pintype "bidirectional"))
      (node (ref "SMA-IN5") (pin "CLK") (pinfunction "1_CLK") (pintype "passive"))
      (node (ref "U$6") (pin "2") (pinfunction "P$2_2") (pintype "bidirectional"))
    )
    (net (code "8") (name "AIN6") (class "Default")
      (node (ref "BNC-IN6") (pin "1") (pinfunction "1_1") (pintype "passive"))
      (node (ref "HEADER-IN") (pin "9") (pinfunction "9_9") (pintype "passive"))
      (node (ref "J4") (pin "5") (pinfunction "5_5") (pintype "bidirectional"))
      (node (ref "SCREW-IN") (pin "7") (pinfunction "7_7") (pintype "bidirectional"))
      (node (ref "SCREW-OUT1") (pin "7") (pinfunction "7_7") (pintype "bidirectional"))
      (node (ref "SMA-IN6") (pin "CLK") (pinfunction "1_CLK") (pintype "passive"))
      (node (ref "U$7") (pin "2") (pinfunction "P$2_2") (pintype "bidirectional"))
    )
    (net (code "9") (name "AIN7") (class "Default")
      (node (ref "BNC-IN7") (pin "1") (pinfunction "1_1") (pintype "passive"))
      (node (ref "HEADER-IN") (pin "10") (pinfunction "10_10") (pintype "passive"))
      (node (ref "J4") (pin "18") (pinfunction "18_18") (pintype "bidirectional"))
      (node (ref "SCREW-IN") (pin "8") (pinfunction "8_8") (pintype "bidirectional"))
      (node (ref "SCREW-OUT1") (pin "8") (pinfunction "8_8") (pintype "bidirectional"))
      (node (ref "SMA-IN7") (pin "CLK") (pinfunction "1_CLK") (pintype "passive"))
      (node (ref "U$8") (pin "2") (pinfunction "P$2_2") (pintype "bidirectional"))
    )
    (net (code "10") (name "AIN8") (class "Default")
      (node (ref "BNC-IN8") (pin "1") (pinfunction "1_1") (pintype "passive"))
      (node (ref "HEADER-IN") (pin "11") (pinfunction "11_11") (pintype "passive"))
      (node (ref "J4") (pin "22") (pinfunction "22_22") (pintype "bidirectional"))
      (node (ref "SMA-IN8") (pin "CLK") (pinfunction "1_CLK") (pintype "passive"))
      (node (ref "U$17") (pin "2") (pinfunction "P$2_2") (pintype "bidirectional"))
    )
    (net (code "11") (name "AIN9") (class "Default")
      (node (ref "BNC-IN9") (pin "1") (pinfunction "1_1") (pintype "passive"))
      (node (ref "HEADER-IN") (pin "12") (pinfunction "12_12") (pintype "passive"))
      (node (ref "J4") (pin "9") (pinfunction "9_9") (pintype "bidirectional"))
      (node (ref "SMA-IN9") (pin "CLK") (pinfunction "1_CLK") (pintype "passive"))
      (node (ref "U$18") (pin "2") (pinfunction "P$2_2") (pintype "bidirectional"))
    )
    (net (code "12") (name "AIN10") (class "Default")
      (node (ref "BNC-IN10") (pin "1") (pinfunction "1_1") (pintype "passive"))
      (node (ref "HEADER-IN") (pin "13") (pinfunction "13_13") (pintype "passive"))
      (node (ref "J4") (pin "21") (pinfunction "21_21") (pintype "bidirectional"))
      (node (ref "SMA-IN10") (pin "CLK") (pinfunction "1_CLK") (pintype "passive"))
      (node (ref "U$19") (pin "2") (pinfunction "P$2_2") (pintype "bidirectional"))
    )
    (net (code "13") (name "AIN11") (class "Default")
      (node (ref "BNC-IN11") (pin "1") (pinfunction "1_1") (pintype "passive"))
      (node (ref "HEADER-IN") (pin "14") (pinfunction "14_14") (pintype "passive"))
      (node (ref "J4") (pin "8") (pinfunction "8_8") (pintype "bidirectional"))
      (node (ref "SMA-IN11") (pin "CLK") (pinfunction "1_CLK") (pintype "passive"))
      (node (ref "U$20") (pin "2") (pinfunction "P$2_2") (pintype "bidirectional"))
    )
    (net (code "14") (name "AIN12") (class "Default")
      (node (ref "BNC-IN12") (pin "1") (pinfunction "1_1") (pintype "passive"))
      (node (ref "HEADER-IN") (pin "15") (pinfunction "15_15") (pintype "passive"))
      (node (ref "J4") (pin "20") (pinfunction "20_20") (pintype "bidirectional"))
      (node (ref "SMA-IN12") (pin "CLK") (pinfunction "1_CLK") (pintype "passive"))
      (node (ref "U$21") (pin "2") (pinfunction "P$2_2") (pintype "bidirectional"))
    )
    (net (code "15") (name "AIN13") (class "Default")
      (node (ref "BNC-IN13") (pin "1") (pinfunction "1_1") (pintype "passive"))
      (node (ref "HEADER-IN") (pin "16") (pinfunction "16_16") (pintype "passive"))
      (node (ref "J4") (pin "7") (pinfunction "7_7") (pintype "bidirectional"))
      (node (ref "SMA-IN13") (pin "CLK") (pinfunction "1_CLK") (pintype "passive"))
      (node (ref "U$22") (pin "2") (pinfunction "P$2_2") (pintype "bidirectional"))
    )
    (net (code "16") (name "AIN14") (class "Default")
      (node (ref "BNC-IN14") (pin "1") (pinfunction "1_1") (pintype "passive"))
      (node (ref "HEADER-IN") (pin "17") (pinfunction "17_17") (pintype "passive"))
      (node (ref "J4") (pin "19") (pinfunction "19_19") (pintype "bidirectional"))
      (node (ref "SMA-IN14") (pin "CLK") (pinfunction "1_CLK") (pintype "passive"))
      (node (ref "U$23") (pin "2") (pinfunction "P$2_2") (pintype "bidirectional"))
    )
    (net (code "17") (name "AIN15") (class "Default")
      (node (ref "BNC-IN15") (pin "1") (pinfunction "1_1") (pintype "passive"))
      (node (ref "HEADER-IN") (pin "18") (pinfunction "18_18") (pintype "passive"))
      (node (ref "J4") (pin "6") (pinfunction "6_6") (pintype "bidirectional"))
      (node (ref "SMA-IN15") (pin "CLK") (pinfunction "1_CLK") (pintype "passive"))
      (node (ref "U$24") (pin "2") (pinfunction "P$2_2") (pintype "bidirectional"))
    )
    (net (code "18") (name "AOUT0") (class "Default")
      (node (ref "BNC-OUT0") (pin "1") (pinfunction "1_1") (pintype "passive"))
      (node (ref "HEADER-OUT") (pin "3") (pinfunction "3_3") (pintype "passive"))
      (node (ref "HEADER-OUT") (pin "4") (pinfunction "4_4") (pintype "passive"))
      (node (ref "J4") (pin "1") (pinfunction "1_1") (pintype "bidirectional"))
      (node (ref "SCREW-OUT") (pin "1") (pinfunction "1_1") (pintype "bidirectional"))
      (node (ref "SCREW-OUT2") (pin "1") (pinfunction "1_1") (pintype "bidirectional"))
      (node (ref "SMA-OUT0") (pin "CLK") (pinfunction "1_CLK") (pintype "passive"))
      (node (ref "U$9") (pin "2") (pinfunction "P$2_2") (pintype "bidirectional"))
      (node (ref "X1") (pin "3") (pinfunction "3_3") (pintype "passive"))
    )
    (net (code "19") (name "AOUT1") (class "Default")
      (node (ref "BNC-OUT1") (pin "1") (pinfunction "1_1") (pintype "passive"))
      (node (ref "HEADER-OUT") (pin "5") (pinfunction "5_5") (pintype "passive"))
      (node (ref "HEADER-OUT") (pin "6") (pinfunction "6_6") (pintype "passive"))
      (node (ref "J4") (pin "26") (pinfunction "26_26") (pintype "bidirectional"))
      (node (ref "SCREW-OUT") (pin "2") (pinfunction "2_2") (pintype "bidirectional"))
      (node (ref "SCREW-OUT2") (pin "2") (pinfunction "2_2") (pintype "bidirectional"))
      (node (ref "SMA-OUT1") (pin "CLK") (pinfunction "1_CLK") (pintype "passive"))
      (node (ref "U$10") (pin "2") (pinfunction "P$2_2") (pintype "bidirectional"))
      (node (ref "X1") (pin "1") (pinfunction "1_1") (pintype "passive"))
    )
    (net (code "20") (name "AOUT2") (class "Default")
      (node (ref "BNC-OUT2") (pin "1") (pinfunction "1_1") (pintype "passive"))
      (node (ref "HEADER-OUT") (pin "7") (pinfunction "7_7") (pintype "passive"))
      (node (ref "HEADER-OUT") (pin "8") (pinfunction "8_8") (pintype "passive"))
      (node (ref "J4") (pin "25") (pinfunction "25_25") (pintype "bidirectional"))
      (node (ref "SCREW-OUT") (pin "3") (pinfunction "3_3") (pintype "bidirectional"))
      (node (ref "SCREW-OUT2") (pin "3") (pinfunction "3_3") (pintype "bidirectional"))
      (node (ref "SMA-OUT2") (pin "CLK") (pinfunction "1_CLK") (pintype "passive"))
      (node (ref "U$11") (pin "2") (pinfunction "P$2_2") (pintype "bidirectional"))
    )
    (net (code "21") (name "AOUT3") (class "Default")
      (node (ref "BNC-OUT3") (pin "1") (pinfunction "1_1") (pintype "passive"))
      (node (ref "HEADER-OUT") (pin "10") (pinfunction "10_10") (pintype "passive"))
      (node (ref "HEADER-OUT") (pin "9") (pinfunction "9_9") (pintype "passive"))
      (node (ref "J4") (pin "12") (pinfunction "12_12") (pintype "bidirectional"))
      (node (ref "SCREW-OUT") (pin "4") (pinfunction "4_4") (pintype "bidirectional"))
      (node (ref "SCREW-OUT2") (pin "4") (pinfunction "4_4") (pintype "bidirectional"))
      (node (ref "SMA-OUT3") (pin "CLK") (pinfunction "1_CLK") (pintype "passive"))
      (node (ref "U$12") (pin "2") (pinfunction "P$2_2") (pintype "bidirectional"))
    )
    (net (code "22") (name "AOUT4") (class "Default")
      (node (ref "BNC-OUT4") (pin "1") (pinfunction "1_1") (pintype "passive"))
      (node (ref "HEADER-OUT") (pin "11") (pinfunction "11_11") (pintype "passive"))
      (node (ref "HEADER-OUT") (pin "12") (pinfunction "12_12") (pintype "passive"))
      (node (ref "J4") (pin "24") (pinfunction "24_24") (pintype "bidirectional"))
      (node (ref "SCREW-OUT") (pin "5") (pinfunction "5_5") (pintype "bidirectional"))
      (node (ref "SCREW-OUT2") (pin "5") (pinfunction "5_5") (pintype "bidirectional"))
      (node (ref "SMA-OUT4") (pin "CLK") (pinfunction "1_CLK") (pintype "passive"))
      (node (ref "U$13") (pin "2") (pinfunction "P$2_2") (pintype "bidirectional"))
    )
    (net (code "23") (name "AOUT5") (class "Default")
      (node (ref "BNC-OUT5") (pin "1") (pinfunction "1_1") (pintype "passive"))
      (node (ref "HEADER-OUT") (pin "13") (pinfunction "13_13") (pintype "passive"))
      (node (ref "HEADER-OUT") (pin "14") (pinfunction "14_14") (pintype "passive"))
      (node (ref "J4") (pin "11") (pinfunction "11_11") (pintype "bidirectional"))
      (node (ref "SCREW-OUT") (pin "6") (pinfunction "6_6") (pintype "bidirectional"))
      (node (ref "SCREW-OUT2") (pin "6") (pinfunction "6_6") (pintype "bidirectional"))
      (node (ref "SMA-OUT5") (pin "CLK") (pinfunction "1_CLK") (pintype "passive"))
      (node (ref "U$14") (pin "2") (pinfunction "P$2_2") (pintype "bidirectional"))
    )
    (net (code "24") (name "AOUT6") (class "Default")
      (node (ref "BNC-OUT6") (pin "1") (pinfunction "1_1") (pintype "passive"))
      (node (ref "HEADER-OUT") (pin "15") (pinfunction "15_15") (pintype "passive"))
      (node (ref "HEADER-OUT") (pin "16") (pinfunction "16_16") (pintype "passive"))
      (node (ref "J4") (pin "23") (pinfunction "23_23") (pintype "bidirectional"))
      (node (ref "SCREW-OUT") (pin "7") (pinfunction "7_7") (pintype "bidirectional"))
      (node (ref "SCREW-OUT2") (pin "7") (pinfunction "7_7") (pintype "bidirectional"))
      (node (ref "SMA-OUT6") (pin "CLK") (pinfunction "1_CLK") (pintype "passive"))
      (node (ref "U$15") (pin "2") (pinfunction "P$2_2") (pintype "bidirectional"))
    )
    (net (code "25") (name "AOUT7") (class "Default")
      (node (ref "BNC-OUT7") (pin "1") (pinfunction "1_1") (pintype "passive"))
      (node (ref "HEADER-OUT") (pin "17") (pinfunction "17_17") (pintype "passive"))
      (node (ref "HEADER-OUT") (pin "18") (pinfunction "18_18") (pintype "passive"))
      (node (ref "J4") (pin "10") (pinfunction "10_10") (pintype "bidirectional"))
      (node (ref "SCREW-OUT") (pin "8") (pinfunction "8_8") (pintype "bidirectional"))
      (node (ref "SCREW-OUT2") (pin "8") (pinfunction "8_8") (pintype "bidirectional"))
      (node (ref "SMA-OUT7") (pin "CLK") (pinfunction "1_CLK") (pintype "passive"))
      (node (ref "U$16") (pin "2") (pinfunction "P$2_2") (pintype "bidirectional"))
    )
    (net (code "26") (name "unconnected-(X1-2-Pad2@2)") (class "Default")
      (node (ref "X1") (pin "2@2") (pinfunction "2_2@2") (pintype "passive"))
    )
  )
)
